# MCU.net
KiCad netlist of a schematic drawn in Altium Designer
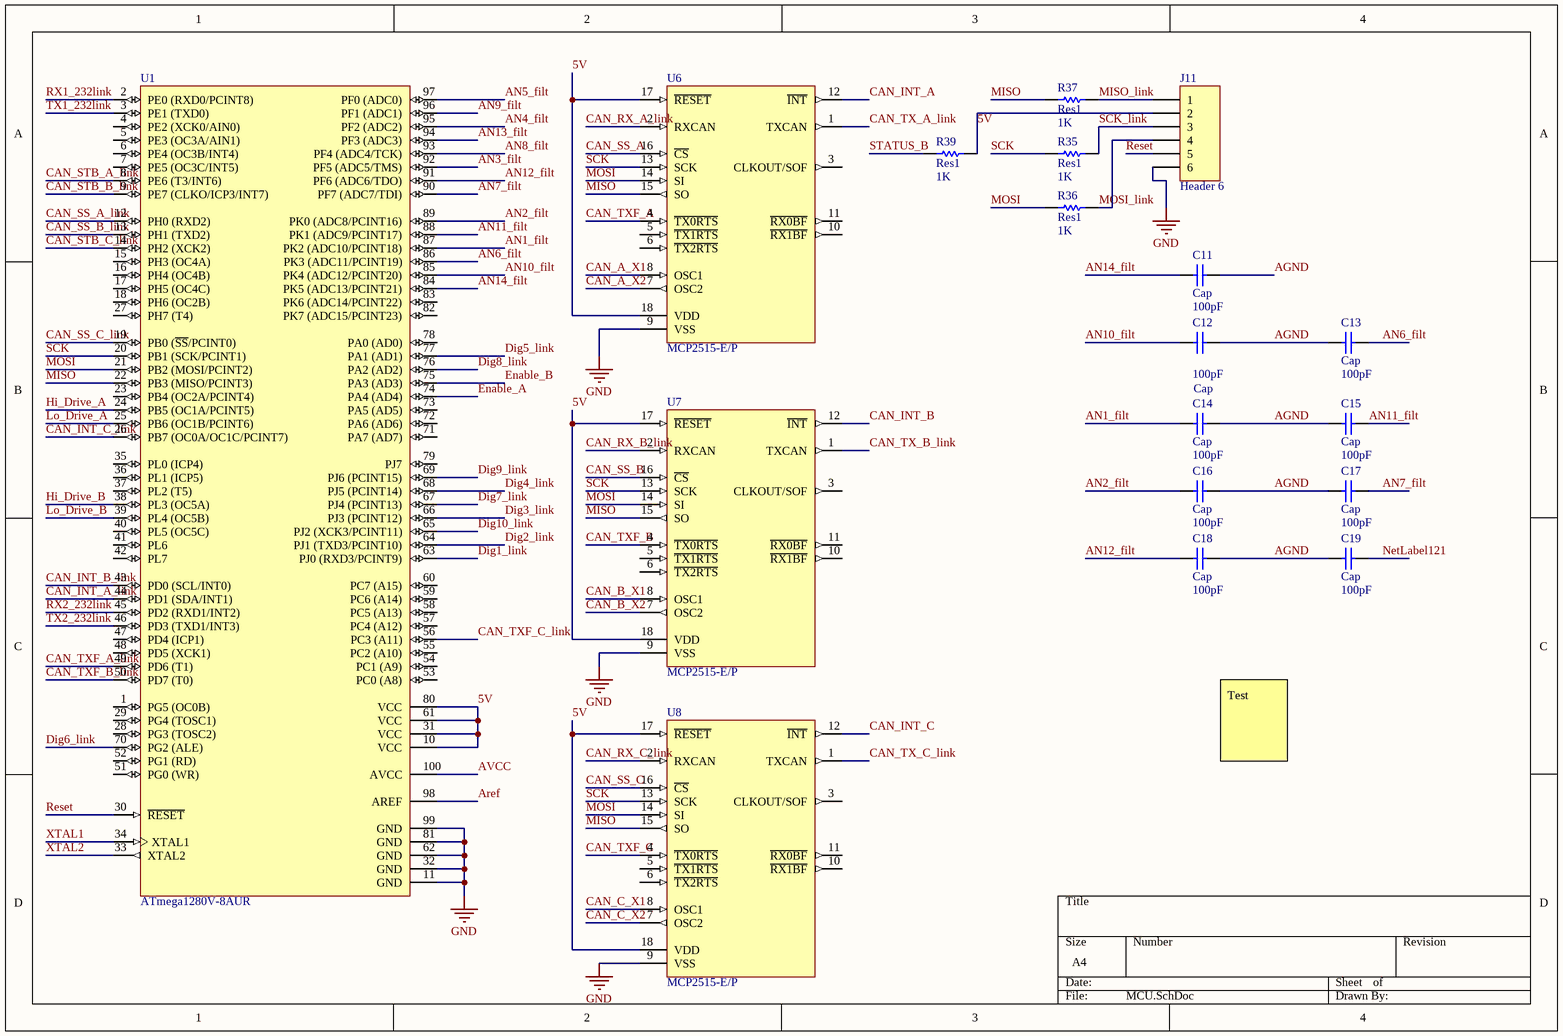
[diagram p0: MCU.SchDoc]

(export (version "E")
  (design (tool "Eeschema 10.0.6"))
  (components
    (comp (ref "C11")
      (value "Cap")
      (footprint "RAD-0.3")
      (description "Capacitor")
      (fields (field (name "ALTIUM_VALUE") "100pF") (field (name "PUBLISHER") "Altium Limited"))
      (libsource (lib "Miscellaneous Devices") (part "Cap"))
    )
    (comp (ref "C12")
      (value "Cap")
      (footprint "RAD-0.3")
      (description "Capacitor")
      (fields (field (name "ALTIUM_VALUE") "100pF") (field (name "PUBLISHER") "Altium Limited"))
      (libsource (lib "Miscellaneous Devices") (part "Cap"))
    )
    (comp (ref "C13")
      (value "Cap")
      (footprint "RAD-0.3")
      (description "Capacitor")
      (fields (field (name "ALTIUM_VALUE") "100pF") (field (name "PUBLISHER") "Altium Limited"))
      (libsource (lib "Miscellaneous Devices") (part "Cap"))
    )
    (comp (ref "C14")
      (value "Cap")
      (footprint "RAD-0.3")
      (description "Capacitor")
      (fields (field (name "ALTIUM_VALUE") "100pF") (field (name "PUBLISHER") "Altium Limited"))
      (libsource (lib "Miscellaneous Devices") (part "Cap"))
    )
    (comp (ref "C15")
      (value "Cap")
      (footprint "RAD-0.3")
      (description "Capacitor")
      (fields (field (name "ALTIUM_VALUE") "100pF") (field (name "PUBLISHER") "Altium Limited"))
      (libsource (lib "Miscellaneous Devices") (part "Cap"))
    )
    (comp (ref "C16")
      (value "Cap")
      (footprint "RAD-0.3")
      (description "Capacitor")
      (fields (field (name "ALTIUM_VALUE") "100pF") (field (name "PUBLISHER") "Altium Limited"))
      (libsource (lib "Miscellaneous Devices") (part "Cap"))
    )
    (comp (ref "C17")
      (value "Cap")
      (footprint "RAD-0.3")
      (description "Capacitor")
      (fields (field (name "ALTIUM_VALUE") "100pF") (field (name "PUBLISHER") "Altium Limited"))
      (libsource (lib "Miscellaneous Devices") (part "Cap"))
    )
    (comp (ref "C18")
      (value "Cap")
      (footprint "RAD-0.3")
      (description "Capacitor")
      (fields (field (name "ALTIUM_VALUE") "100pF") (field (name "PUBLISHER") "Altium Limited"))
      (libsource (lib "Miscellaneous Devices") (part "Cap"))
    )
    (comp (ref "C19")
      (value "Cap")
      (footprint "RAD-0.3")
      (description "Capacitor")
      (fields (field (name "ALTIUM_VALUE") "100pF") (field (name "PUBLISHER") "Altium Limited"))
      (libsource (lib "Miscellaneous Devices") (part "Cap"))
    )
    (comp (ref "J11")
      (value "Header 6")
      (footprint "HDR1X6")
      (description "Header, 6-Pin")
      (fields (field (name "PUBLISHER") "Altium Limited"))
      (libsource (lib "Miscellaneous Connectors") (part "Header 6"))
    )
    (comp (ref "R35")
      (value "Res1")
      (footprint "AXIAL-0.3")
      (description "Resistor")
      (fields (field (name "ALTIUM_VALUE") "1K") (field (name "PUBLISHER") "Altium Limited"))
      (libsource (lib "Miscellaneous Devices") (part "Res1"))
    )
    (comp (ref "R36")
      (value "Res1")
      (footprint "AXIAL-0.3")
      (description "Resistor")
      (fields (field (name "ALTIUM_VALUE") "1K") (field (name "PUBLISHER") "Altium Limited"))
      (libsource (lib "Miscellaneous Devices") (part "Res1"))
    )
    (comp (ref "R37")
      (value "Res1")
      (footprint "AXIAL-0.3")
      (description "Resistor")
      (fields (field (name "ALTIUM_VALUE") "1K") (field (name "PUBLISHER") "Altium Limited"))
      (libsource (lib "Miscellaneous Devices") (part "Res1"))
    )
    (comp (ref "R39")
      (value "Res1")
      (footprint "AXIAL-0.3")
      (description "Resistor")
      (fields (field (name "ALTIUM_VALUE") "1K") (field (name "PUBLISHER") "Altium Limited"))
      (libsource (lib "Miscellaneous Devices") (part "Res1"))
    )
    (comp (ref "U1")
      (value "ATmega1280V-8AUR")
      (footprint "100A_M")
      (libsource (lib "Altium Content Vault") (part "MC-8B-ATM640-SQ100"))
    )
    (comp (ref "U6")
      (value "MCP2515-E/P")
      (footprint "PDIP300-P18")
      (description "Stand-Alone CAN Controller With SPI Interface, 18-Pin PDIP, Extended Temperature")
      (libsource (lib "Altium Content Vault") (part "COM-CAN-MCP2515-18"))
    )
    (comp (ref "U7")
      (value "MCP2515-E/P")
      (footprint "PDIP300-P18")
      (description "Stand-Alone CAN Controller With SPI Interface, 18-Pin PDIP, Extended Temperature")
      (libsource (lib "Altium Content Vault") (part "COM-CAN-MCP2515-18"))
    )
    (comp (ref "U8")
      (value "MCP2515-E/P")
      (footprint "PDIP300-P18")
      (description "Stand-Alone CAN Controller With SPI Interface, 18-Pin PDIP, Extended Temperature")
      (libsource (lib "Altium Content Vault") (part "COM-CAN-MCP2515-18"))
    )
  )
  (nets
    (net (code "1") (name "/5V") (class "Default")
      (node (ref "J11") (pin "2") (pinfunction "2_2") (pintype "passive"))
      (node (ref "R39") (pin "2") (pinfunction "2_2") (pintype "passive"))
      (node (ref "U1") (pin "10") (pinfunction "VCC_10") (pintype "power_in"))
      (node (ref "U1") (pin "31") (pinfunction "VCC_31") (pintype "power_in"))
      (node (ref "U1") (pin "61") (pinfunction "VCC_61") (pintype "power_in"))
      (node (ref "U1") (pin "80") (pinfunction "VCC_80") (pintype "power_in"))
      (node (ref "U6") (pin "17") (pinfunction "~{RESET}_17") (pintype "input"))
      (node (ref "U6") (pin "18") (pinfunction "VDD_18") (pintype "power_in"))
      (node (ref "U7") (pin "17") (pinfunction "~{RESET}_17") (pintype "input"))
      (node (ref "U7") (pin "18") (pinfunction "VDD_18") (pintype "power_in"))
      (node (ref "U8") (pin "17") (pinfunction "~{RESET}_17") (pintype "input"))
      (node (ref "U8") (pin "18") (pinfunction "VDD_18") (pintype "power_in"))
    )
    (net (code "2") (name "/AGND") (class "Default")
      (node (ref "C11") (pin "2") (pinfunction "2_2") (pintype "passive"))
      (node (ref "C12") (pin "2") (pinfunction "2_2") (pintype "passive"))
      (node (ref "C13") (pin "1") (pinfunction "1_1") (pintype "passive"))
      (node (ref "C14") (pin "2") (pinfunction "2_2") (pintype "passive"))
      (node (ref "C15") (pin "1") (pinfunction "1_1") (pintype "passive"))
      (node (ref "C16") (pin "2") (pinfunction "2_2") (pintype "passive"))
      (node (ref "C17") (pin "1") (pinfunction "1_1") (pintype "passive"))
      (node (ref "C18") (pin "2") (pinfunction "2_2") (pintype "passive"))
      (node (ref "C19") (pin "1") (pinfunction "1_1") (pintype "passive"))
    )
    (net (code "3") (name "/AN1_filt") (class "Default")
      (node (ref "C14") (pin "1") (pinfunction "1_1") (pintype "passive"))
      (node (ref "U1") (pin "87") (pinfunction "PK2_(ADC10/PCINT18)_87") (pintype "bidirectional"))
    )
    (net (code "4") (name "/AN2_filt") (class "Default")
      (node (ref "C16") (pin "1") (pinfunction "1_1") (pintype "passive"))
      (node (ref "U1") (pin "89") (pinfunction "PK0_(ADC8/PCINT16)_89") (pintype "bidirectional"))
    )
    (net (code "5") (name "/AN3_filt") (class "Default")
      (node (ref "U1") (pin "92") (pinfunction "PF5_(ADC5/TMS)_92") (pintype "bidirectional"))
    )
    (net (code "6") (name "/AN4_filt") (class "Default")
      (node (ref "U1") (pin "95") (pinfunction "PF2_(ADC2)_95") (pintype "bidirectional"))
    )
    (net (code "7") (name "/AN5_filt") (class "Default")
      (node (ref "U1") (pin "97") (pinfunction "PF0_(ADC0)_97") (pintype "bidirectional"))
    )
    (net (code "8") (name "/AN6_filt") (class "Default")
      (node (ref "C13") (pin "2") (pinfunction "2_2") (pintype "passive"))
      (node (ref "U1") (pin "86") (pinfunction "PK3_(ADC11/PCINT19)_86") (pintype "bidirectional"))
    )
    (net (code "9") (name "/AN7_filt") (class "Default")
      (node (ref "C17") (pin "2") (pinfunction "2_2") (pintype "passive"))
      (node (ref "U1") (pin "90") (pinfunction "PF7_(ADC7/TDI)_90") (pintype "bidirectional"))
    )
    (net (code "10") (name "/AN8_filt") (class "Default")
      (node (ref "U1") (pin "93") (pinfunction "PF4_(ADC4/TCK)_93") (pintype "bidirectional"))
    )
    (net (code "11") (name "/AN9_filt") (class "Default")
      (node (ref "U1") (pin "96") (pinfunction "PF1_(ADC1)_96") (pintype "bidirectional"))
    )
    (net (code "12") (name "/AN10_filt") (class "Default")
      (node (ref "C12") (pin "1") (pinfunction "1_1") (pintype "passive"))
      (node (ref "U1") (pin "85") (pinfunction "PK4_(ADC12/PCINT20)_85") (pintype "bidirectional"))
    )
    (net (code "13") (name "/AN11_filt") (class "Default")
      (node (ref "C15") (pin "2") (pinfunction "2_2") (pintype "passive"))
      (node (ref "U1") (pin "88") (pinfunction "PK1_(ADC9/PCINT17)_88") (pintype "bidirectional"))
    )
    (net (code "14") (name "/AN12_filt") (class "Default")
      (node (ref "C18") (pin "1") (pinfunction "1_1") (pintype "passive"))
      (node (ref "U1") (pin "91") (pinfunction "PF6_(ADC6/TDO)_91") (pintype "bidirectional"))
    )
    (net (code "15") (name "/AN13_filt") (class "Default")
      (node (ref "U1") (pin "94") (pinfunction "PF3_(ADC3)_94") (pintype "bidirectional"))
    )
    (net (code "16") (name "/AN14_filt") (class "Default")
      (node (ref "C11") (pin "1") (pinfunction "1_1") (pintype "passive"))
      (node (ref "U1") (pin "84") (pinfunction "PK5_(ADC13/PCINT21)_84") (pintype "bidirectional"))
    )
    (net (code "17") (name "/AVCC") (class "Default")
      (node (ref "U1") (pin "100") (pinfunction "AVCC_100") (pintype "power_in"))
    )
    (net (code "18") (name "/Aref") (class "Default")
      (node (ref "U1") (pin "98") (pinfunction "AREF_98") (pintype "power_in"))
    )
    (net (code "19") (name "/CAN_A_X1") (class "Default")
      (node (ref "U6") (pin "8") (pinfunction "OSC1_8") (pintype "input"))
    )
    (net (code "20") (name "/CAN_A_X2") (class "Default")
      (node (ref "U6") (pin "7") (pinfunction "OSC2_7") (pintype "output"))
    )
    (net (code "21") (name "/CAN_B_X1") (class "Default")
      (node (ref "U7") (pin "8") (pinfunction "OSC1_8") (pintype "input"))
    )
    (net (code "22") (name "/CAN_B_X2") (class "Default")
      (node (ref "U7") (pin "7") (pinfunction "OSC2_7") (pintype "output"))
    )
    (net (code "23") (name "/CAN_C_X1") (class "Default")
      (node (ref "U8") (pin "8") (pinfunction "OSC1_8") (pintype "input"))
    )
    (net (code "24") (name "/CAN_C_X2") (class "Default")
      (node (ref "U8") (pin "7") (pinfunction "OSC2_7") (pintype "output"))
    )
    (net (code "25") (name "/CAN_INT_A") (class "Default")
      (node (ref "U6") (pin "12") (pinfunction "~{INT}_12") (pintype "output"))
    )
    (net (code "26") (name "/CAN_INT_A_link") (class "Default")
      (node (ref "U1") (pin "44") (pinfunction "PD1_(SDA/INT1)_44") (pintype "bidirectional"))
    )
    (net (code "27") (name "/CAN_INT_B") (class "Default")
      (node (ref "U7") (pin "12") (pinfunction "~{INT}_12") (pintype "output"))
    )
    (net (code "28") (name "/CAN_INT_B_link") (class "Default")
      (node (ref "U1") (pin "43") (pinfunction "PD0_(SCL/INT0)_43") (pintype "bidirectional"))
    )
    (net (code "29") (name "/CAN_INT_C") (class "Default")
      (node (ref "U8") (pin "12") (pinfunction "~{INT}_12") (pintype "output"))
    )
    (net (code "30") (name "/CAN_INT_C_link") (class "Default")
      (node (ref "U1") (pin "26") (pinfunction "PB7_(OC0A/OC1C/PCINT7)_26") (pintype "bidirectional"))
    )
    (net (code "31") (name "/CAN_RX_A_link") (class "Default")
      (node (ref "U6") (pin "2") (pinfunction "RXCAN_2") (pintype "input"))
    )
    (net (code "32") (name "/CAN_RX_B_link") (class "Default")
      (node (ref "U7") (pin "2") (pinfunction "RXCAN_2") (pintype "input"))
    )
    (net (code "33") (name "/CAN_RX_C_link") (class "Default")
      (node (ref "U8") (pin "2") (pinfunction "RXCAN_2") (pintype "input"))
    )
    (net (code "34") (name "/CAN_SS_A") (class "Default")
      (node (ref "U6") (pin "16") (pinfunction "~{CS}_16") (pintype "input"))
    )
    (net (code "35") (name "/CAN_SS_A_link") (class "Default")
      (node (ref "U1") (pin "12") (pinfunction "PH0_(RXD2)_12") (pintype "bidirectional"))
    )
    (net (code "36") (name "/CAN_SS_B") (class "Default")
      (node (ref "U7") (pin "16") (pinfunction "~{CS}_16") (pintype "input"))
    )
    (net (code "37") (name "/CAN_SS_B_link") (class "Default")
      (node (ref "U1") (pin "13") (pinfunction "PH1_(TXD2)_13") (pintype "bidirectional"))
    )
    (net (code "38") (name "/CAN_SS_C") (class "Default")
      (node (ref "U8") (pin "16") (pinfunction "~{CS}_16") (pintype "input"))
    )
    (net (code "39") (name "/CAN_SS_C_link") (class "Default")
      (node (ref "U1") (pin "19") (pinfunction "PB0_(~{SS}/PCINT0)_19") (pintype "bidirectional"))
    )
    (net (code "40") (name "/CAN_STB_A_link") (class "Default")
      (node (ref "U1") (pin "8") (pinfunction "PE6_(T3/INT6)_8") (pintype "bidirectional"))
    )
    (net (code "41") (name "/CAN_STB_B_link") (class "Default")
      (node (ref "U1") (pin "9") (pinfunction "PE7_(CLKO/ICP3/INT7)_9") (pintype "bidirectional"))
    )
    (net (code "42") (name "/CAN_STB_C_link") (class "Default")
      (node (ref "U1") (pin "14") (pinfunction "PH2_(XCK2)_14") (pintype "bidirectional"))
    )
    (net (code "43") (name "/CAN_TXF_A") (class "Default")
      (node (ref "U6") (pin "4") (pinfunction "~{TX0RTS}_4") (pintype "input"))
    )
    (net (code "44") (name "/CAN_TXF_A_link") (class "Default")
      (node (ref "U1") (pin "49") (pinfunction "PD6_(T1)_49") (pintype "bidirectional"))
    )
    (net (code "45") (name "/CAN_TXF_B") (class "Default")
      (node (ref "U7") (pin "4") (pinfunction "~{TX0RTS}_4") (pintype "input"))
    )
    (net (code "46") (name "/CAN_TXF_B_link") (class "Default")
      (node (ref "U1") (pin "50") (pinfunction "PD7_(T0)_50") (pintype "bidirectional"))
    )
    (net (code "47") (name "/CAN_TXF_C") (class "Default")
      (node (ref "U8") (pin "4") (pinfunction "~{TX0RTS}_4") (pintype "input"))
    )
    (net (code "48") (name "/CAN_TXF_C_link") (class "Default")
      (node (ref "U1") (pin "56") (pinfunction "PC3_(A11)_56") (pintype "bidirectional"))
    )
    (net (code "49") (name "/CAN_TX_A_link") (class "Default")
      (node (ref "U6") (pin "1") (pinfunction "TXCAN_1") (pintype "output"))
    )
    (net (code "50") (name "/CAN_TX_B_link") (class "Default")
      (node (ref "U7") (pin "1") (pinfunction "TXCAN_1") (pintype "output"))
    )
    (net (code "51") (name "/CAN_TX_C_link") (class "Default")
      (node (ref "U8") (pin "1") (pinfunction "TXCAN_1") (pintype "output"))
    )
    (net (code "52") (name "/Dig1_link") (class "Default")
      (node (ref "U1") (pin "63") (pinfunction "PJ0_(RXD3/PCINT9)_63") (pintype "bidirectional"))
    )
    (net (code "53") (name "/Dig2_link") (class "Default")
      (node (ref "U1") (pin "64") (pinfunction "PJ1_(TXD3/PCINT10)_64") (pintype "bidirectional"))
    )
    (net (code "54") (name "/Dig3_link") (class "Default")
      (node (ref "U1") (pin "66") (pinfunction "PJ3_(PCINT12)_66") (pintype "bidirectional"))
    )
    (net (code "55") (name "/Dig4_link") (class "Default")
      (node (ref "U1") (pin "68") (pinfunction "PJ5_(PCINT14)_68") (pintype "bidirectional"))
    )
    (net (code "56") (name "/Dig5_link") (class "Default")
      (node (ref "U1") (pin "77") (pinfunction "PA1_(AD1)_77") (pintype "bidirectional"))
    )
    (net (code "57") (name "/Dig6_link") (class "Default")
      (node (ref "U1") (pin "70") (pinfunction "PG2_(ALE)_70") (pintype "bidirectional"))
    )
    (net (code "58") (name "/Dig7_link") (class "Default")
      (node (ref "U1") (pin "67") (pinfunction "PJ4_(PCINT13)_67") (pintype "bidirectional"))
    )
    (net (code "59") (name "/Dig8_link") (class "Default")
      (node (ref "U1") (pin "76") (pinfunction "PA2_(AD2)_76") (pintype "bidirectional"))
    )
    (net (code "60") (name "/Dig9_link") (class "Default")
      (node (ref "U1") (pin "69") (pinfunction "PJ6_(PCINT15)_69") (pintype "bidirectional"))
    )
    (net (code "61") (name "/Dig10_link") (class "Default")
      (node (ref "U1") (pin "65") (pinfunction "PJ2_(XCK3/PCINT11)_65") (pintype "bidirectional"))
    )
    (net (code "62") (name "/Enable_A") (class "Default")
      (node (ref "U1") (pin "74") (pinfunction "PA4_(AD4)_74") (pintype "bidirectional"))
    )
    (net (code "63") (name "/Enable_B") (class "Default")
      (node (ref "U1") (pin "75") (pinfunction "PA3_(AD3)_75") (pintype "bidirectional"))
    )
    (net (code "64") (name "/Hi_Drive_A") (class "Default")
      (node (ref "U1") (pin "24") (pinfunction "PB5_(OC1A/PCINT5)_24") (pintype "bidirectional"))
    )
    (net (code "65") (name "/Hi_Drive_B") (class "Default")
      (node (ref "U1") (pin "38") (pinfunction "PL3_(OC5A)_38") (pintype "bidirectional"))
    )
    (net (code "66") (name "/Lo_Drive_A") (class "Default")
      (node (ref "U1") (pin "25") (pinfunction "PB6_(OC1B/PCINT6)_25") (pintype "bidirectional"))
    )
    (net (code "67") (name "/Lo_Drive_B") (class "Default")
      (node (ref "U1") (pin "39") (pinfunction "PL4_(OC5B)_39") (pintype "bidirectional"))
    )
    (net (code "68") (name "/MISO") (class "Default")
      (node (ref "R37") (pin "1") (pinfunction "1_1") (pintype "passive"))
      (node (ref "U1") (pin "22") (pinfunction "PB3_(MISO/PCINT3)_22") (pintype "bidirectional"))
      (node (ref "U6") (pin "15") (pinfunction "SO_15") (pintype "output"))
      (node (ref "U7") (pin "15") (pinfunction "SO_15") (pintype "output"))
      (node (ref "U8") (pin "15") (pinfunction "SO_15") (pintype "output"))
    )
    (net (code "69") (name "/MISO_link") (class "Default")
      (node (ref "J11") (pin "1") (pinfunction "1_1") (pintype "passive"))
      (node (ref "R37") (pin "2") (pinfunction "2_2") (pintype "passive"))
    )
    (net (code "70") (name "/MOSI") (class "Default")
      (node (ref "R36") (pin "1") (pinfunction "1_1") (pintype "passive"))
      (node (ref "U1") (pin "21") (pinfunction "PB2_(MOSI/PCINT2)_21") (pintype "bidirectional"))
      (node (ref "U6") (pin "14") (pinfunction "SI_14") (pintype "input"))
      (node (ref "U7") (pin "14") (pinfunction "SI_14") (pintype "input"))
      (node (ref "U8") (pin "14") (pinfunction "SI_14") (pintype "input"))
    )
    (net (code "71") (name "/MOSI_link") (class "Default")
      (node (ref "J11") (pin "4") (pinfunction "4_4") (pintype "passive"))
      (node (ref "R36") (pin "2") (pinfunction "2_2") (pintype "passive"))
    )
    (net (code "72") (name "/NetLabel121") (class "Default")
      (node (ref "C19") (pin "2") (pinfunction "2_2") (pintype "passive"))
    )
    (net (code "73") (name "/RX1_232link") (class "Default")
      (node (ref "U1") (pin "2") (pinfunction "PE0_(RXD0/PCINT8)_2") (pintype "bidirectional"))
    )
    (net (code "74") (name "/RX2_232link") (class "Default")
      (node (ref "U1") (pin "45") (pinfunction "PD2_(RXD1/INT2)_45") (pintype "bidirectional"))
    )
    (net (code "75") (name "/Reset") (class "Default")
      (node (ref "J11") (pin "5") (pinfunction "5_5") (pintype "passive"))
      (node (ref "U1") (pin "30") (pinfunction "~{RESET}_30") (pintype "input"))
    )
    (net (code "76") (name "/SCK") (class "Default")
      (node (ref "R35") (pin "1") (pinfunction "1_1") (pintype "passive"))
      (node (ref "U1") (pin "20") (pinfunction "PB1_(SCK/PCINT1)_20") (pintype "bidirectional"))
      (node (ref "U6") (pin "13") (pinfunction "SCK_13") (pintype "input"))
      (node (ref "U7") (pin "13") (pinfunction "SCK_13") (pintype "input"))
      (node (ref "U8") (pin "13") (pinfunction "SCK_13") (pintype "input"))
    )
    (net (code "77") (name "/SCK_link") (class "Default")
      (node (ref "J11") (pin "3") (pinfunction "3_3") (pintype "passive"))
      (node (ref "R35") (pin "2") (pinfunction "2_2") (pintype "passive"))
    )
    (net (code "78") (name "/STATUS_B") (class "Default")
      (node (ref "R39") (pin "1") (pinfunction "1_1") (pintype "passive"))
    )
    (net (code "79") (name "/TX1_232link") (class "Default")
      (node (ref "U1") (pin "3") (pinfunction "PE1_(TXD0)_3") (pintype "bidirectional"))
    )
    (net (code "80") (name "/TX2_232link") (class "Default")
      (node (ref "U1") (pin "46") (pinfunction "PD3_(TXD1/INT3)_46") (pintype "bidirectional"))
    )
    (net (code "81") (name "/XTAL1") (class "Default")
      (node (ref "U1") (pin "34") (pinfunction "XTAL1_34") (pintype "input"))
    )
    (net (code "82") (name "/XTAL2") (class "Default")
      (node (ref "U1") (pin "33") (pinfunction "XTAL2_33") (pintype "output"))
    )
    (net (code "83") (name "GND") (class "Default")
      (node (ref "J11") (pin "6") (pinfunction "6_6") (pintype "passive"))
      (node (ref "U1") (pin "11") (pinfunction "GND_11") (pintype "power_in"))
      (node (ref "U1") (pin "32") (pinfunction "GND_32") (pintype "power_in"))
      (node (ref "U1") (pin "62") (pinfunction "GND_62") (pintype "power_in"))
      (node (ref "U1") (pin "81") (pinfunction "GND_81") (pintype "power_in"))
      (node (ref "U1") (pin "99") (pinfunction "GND_99") (pintype "power_in"))
      (node (ref "U6") (pin "9") (pinfunction "VSS_9") (pintype "power_in"))
      (node (ref "U7") (pin "9") (pinfunction "VSS_9") (pintype "power_in"))
      (node (ref "U8") (pin "9") (pinfunction "VSS_9") (pintype "power_in"))
    )
    (net (code "84") (name "unconnected-(U1-PA0_(AD0)-Pad78)") (class "Default")
      (node (ref "U1") (pin "78") (pinfunction "PA0_(AD0)_78") (pintype "bidirectional"))
    )
    (net (code "85") (name "unconnected-(U1-PA5_(AD5)-Pad73)") (class "Default")
      (node (ref "U1") (pin "73") (pinfunction "PA5_(AD5)_73") (pintype "bidirectional"))
    )
    (net (code "86") (name "unconnected-(U1-PA6_(AD6)-Pad72)") (class "Default")
      (node (ref "U1") (pin "72") (pinfunction "PA6_(AD6)_72") (pintype "bidirectional"))
    )
    (net (code "87") (name "unconnected-(U1-PA7_(AD7)-Pad71)") (class "Default")
      (node (ref "U1") (pin "71") (pinfunction "PA7_(AD7)_71") (pintype "bidirectional"))
    )
    (net (code "88") (name "unconnected-(U1-PB4_(OC2A{slash}PCINT4)-Pad23)") (class "Default")
      (node (ref "U1") (pin "23") (pinfunction "PB4_(OC2A/PCINT4)_23") (pintype "bidirectional"))
    )
    (net (code "89") (name "unconnected-(U1-PC0_(A8)-Pad53)") (class "Default")
      (node (ref "U1") (pin "53") (pinfunction "PC0_(A8)_53") (pintype "bidirectional"))
    )
    (net (code "90") (name "unconnected-(U1-PC1_(A9)-Pad54)") (class "Default")
      (node (ref "U1") (pin "54") (pinfunction "PC1_(A9)_54") (pintype "bidirectional"))
    )
    (net (code "91") (name "unconnected-(U1-PC2_(A10)-Pad55)") (class "Default")
      (node (ref "U1") (pin "55") (pinfunction "PC2_(A10)_55") (pintype "bidirectional"))
    )
    (net (code "92") (name "unconnected-(U1-PC4_(A12)-Pad57)") (class "Default")
      (node (ref "U1") (pin "57") (pinfunction "PC4_(A12)_57") (pintype "bidirectional"))
    )
    (net (code "93") (name "unconnected-(U1-PC5_(A13)-Pad58)") (class "Default")
      (node (ref "U1") (pin "58") (pinfunction "PC5_(A13)_58") (pintype "bidirectional"))
    )
    (net (code "94") (name "unconnected-(U1-PC6_(A14)-Pad59)") (class "Default")
      (node (ref "U1") (pin "59") (pinfunction "PC6_(A14)_59") (pintype "bidirectional"))
    )
    (net (code "95") (name "unconnected-(U1-PC7_(A15)-Pad60)") (class "Default")
      (node (ref "U1") (pin "60") (pinfunction "PC7_(A15)_60") (pintype "bidirectional"))
    )
    (net (code "96") (name "unconnected-(U1-PD4_(ICP1)-Pad47)") (class "Default")
      (node (ref "U1") (pin "47") (pinfunction "PD4_(ICP1)_47") (pintype "bidirectional"))
    )
    (net (code "97") (name "unconnected-(U1-PD5_(XCK1)-Pad48)") (class "Default")
      (node (ref "U1") (pin "48") (pinfunction "PD5_(XCK1)_48") (pintype "bidirectional"))
    )
    (net (code "98") (name "unconnected-(U1-PE2_(XCK0{slash}AIN0)-Pad4)") (class "Default")
      (node (ref "U1") (pin "4") (pinfunction "PE2_(XCK0/AIN0)_4") (pintype "bidirectional"))
    )
    (net (code "99") (name "unconnected-(U1-PE3_(OC3A{slash}AIN1)-Pad5)") (class "Default")
      (node (ref "U1") (pin "5") (pinfunction "PE3_(OC3A/AIN1)_5") (pintype "bidirectional"))
    )
    (net (code "100") (name "unconnected-(U1-PE4_(OC3B{slash}INT4)-Pad6)") (class "Default")
      (node (ref "U1") (pin "6") (pinfunction "PE4_(OC3B/INT4)_6") (pintype "bidirectional"))
    )
    (net (code "101") (name "unconnected-(U1-PE5_(OC3C{slash}INT5)-Pad7)") (class "Default")
      (node (ref "U1") (pin "7") (pinfunction "PE5_(OC3C/INT5)_7") (pintype "bidirectional"))
    )
    (net (code "102") (name "unconnected-(U1-PG0_(WR)-Pad51)") (class "Default")
      (node (ref "U1") (pin "51") (pinfunction "PG0_(WR)_51") (pintype "bidirectional"))
    )
    (net (code "103") (name "unconnected-(U1-PG1_(RD)-Pad52)") (class "Default")
      (node (ref "U1") (pin "52") (pinfunction "PG1_(RD)_52") (pintype "bidirectional"))
    )
    (net (code "104") (name "unconnected-(U1-PG3_(TOSC2)-Pad28)") (class "Default")
      (node (ref "U1") (pin "28") (pinfunction "PG3_(TOSC2)_28") (pintype "bidirectional"))
    )
    (net (code "105") (name "unconnected-(U1-PG4_(TOSC1)-Pad29)") (class "Default")
      (node (ref "U1") (pin "29") (pinfunction "PG4_(TOSC1)_29") (pintype "bidirectional"))
    )
    (net (code "106") (name "unconnected-(U1-PG5_(OC0B)-Pad1)") (class "Default")
      (node (ref "U1") (pin "1") (pinfunction "PG5_(OC0B)_1") (pintype "bidirectional"))
    )
    (net (code "107") (name "unconnected-(U1-PH3_(OC4A)-Pad15)") (class "Default")
      (node (ref "U1") (pin "15") (pinfunction "PH3_(OC4A)_15") (pintype "bidirectional"))
    )
    (net (code "108") (name "unconnected-(U1-PH4_(OC4B)-Pad16)") (class "Default")
      (node (ref "U1") (pin "16") (pinfunction "PH4_(OC4B)_16") (pintype "bidirectional"))
    )
    (net (code "109") (name "unconnected-(U1-PH5_(OC4C)-Pad17)") (class "Default")
      (node (ref "U1") (pin "17") (pinfunction "PH5_(OC4C)_17") (pintype "bidirectional"))
    )
    (net (code "110") (name "unconnected-(U1-PH6_(OC2B)-Pad18)") (class "Default")
      (node (ref "U1") (pin "18") (pinfunction "PH6_(OC2B)_18") (pintype "bidirectional"))
    )
    (net (code "111") (name "unconnected-(U1-PH7_(T4)-Pad27)") (class "Default")
      (node (ref "U1") (pin "27") (pinfunction "PH7_(T4)_27") (pintype "bidirectional"))
    )
    (net (code "112") (name "unconnected-(U1-PJ7-Pad79)") (class "Default")
      (node (ref "U1") (pin "79") (pinfunction "PJ7_79") (pintype "bidirectional"))
    )
    (net (code "113") (name "unconnected-(U1-PK6_(ADC14{slash}PCINT22)-Pad83)") (class "Default")
      (node (ref "U1") (pin "83") (pinfunction "PK6_(ADC14/PCINT22)_83") (pintype "bidirectional"))
    )
    (net (code "114") (name "unconnected-(U1-PK7_(ADC15{slash}PCINT23)-Pad82)") (class "Default")
      (node (ref "U1") (pin "82") (pinfunction "PK7_(ADC15/PCINT23)_82") (pintype "bidirectional"))
    )
    (net (code "115") (name "unconnected-(U1-PL0_(ICP4)-Pad35)") (class "Default")
      (node (ref "U1") (pin "35") (pinfunction "PL0_(ICP4)_35") (pintype "bidirectional"))
    )
    (net (code "116") (name "unconnected-(U1-PL1_(ICP5)-Pad36)") (class "Default")
      (node (ref "U1") (pin "36") (pinfunction "PL1_(ICP5)_36") (pintype "bidirectional"))
    )
    (net (code "117") (name "unconnected-(U1-PL2_(T5)-Pad37)") (class "Default")
      (node (ref "U1") (pin "37") (pinfunction "PL2_(T5)_37") (pintype "bidirectional"))
    )
    (net (code "118") (name "unconnected-(U1-PL5_(OC5C)-Pad40)") (class "Default")
      (node (ref "U1") (pin "40") (pinfunction "PL5_(OC5C)_40") (pintype "bidirectional"))
    )
    (net (code "119") (name "unconnected-(U1-PL6-Pad41)") (class "Default")
      (node (ref "U1") (pin "41") (pinfunction "PL6_41") (pintype "bidirectional"))
    )
    (net (code "120") (name "unconnected-(U1-PL7-Pad42)") (class "Default")
      (node (ref "U1") (pin "42") (pinfunction "PL7_42") (pintype "bidirectional"))
    )
    (net (code "121") (name "unconnected-(U6-CLKOUT{slash}SOF-Pad3)") (class "Default")
      (node (ref "U6") (pin "3") (pinfunction "CLKOUT/SOF_3") (pintype "output"))
    )
    (net (code "122") (name "unconnected-(U6-~{RX0BF}-Pad11)") (class "Default")
      (node (ref "U6") (pin "11") (pinfunction "~{RX0BF}_11") (pintype "output"))
    )
    (net (code "123") (name "unconnected-(U6-~{RX1BF}-Pad10)") (class "Default")
      (node (ref "U6") (pin "10") (pinfunction "~{RX1BF}_10") (pintype "output"))
    )
    (net (code "124") (name "unconnected-(U6-~{TX1RTS}-Pad5)") (class "Default")
      (node (ref "U6") (pin "5") (pinfunction "~{TX1RTS}_5") (pintype "input"))
    )
    (net (code "125") (name "unconnected-(U6-~{TX2RTS}-Pad6)") (class "Default")
      (node (ref "U6") (pin "6") (pinfunction "~{TX2RTS}_6") (pintype "input"))
    )
    (net (code "126") (name "unconnected-(U7-CLKOUT{slash}SOF-Pad3)") (class "Default")
      (node (ref "U7") (pin "3") (pinfunction "CLKOUT/SOF_3") (pintype "output"))
    )
    (net (code "127") (name "unconnected-(U7-~{RX0BF}-Pad11)") (class "Default")
      (node (ref "U7") (pin "11") (pinfunction "~{RX0BF}_11") (pintype "output"))
    )
    (net (code "128") (name "unconnected-(U7-~{RX1BF}-Pad10)") (class "Default")
      (node (ref "U7") (pin "10") (pinfunction "~{RX1BF}_10") (pintype "output"))
    )
    (net (code "129") (name "unconnected-(U7-~{TX1RTS}-Pad5)") (class "Default")
      (node (ref "U7") (pin "5") (pinfunction "~{TX1RTS}_5") (pintype "input"))
    )
    (net (code "130") (name "unconnected-(U7-~{TX2RTS}-Pad6)") (class "Default")
      (node (ref "U7") (pin "6") (pinfunction "~{TX2RTS}_6") (pintype "input"))
    )
    (net (code "131") (name "unconnected-(U8-CLKOUT{slash}SOF-Pad3)") (class "Default")
      (node (ref "U8") (pin "3") (pinfunction "CLKOUT/SOF_3") (pintype "output"))
    )
    (net (code "132") (name "unconnected-(U8-~{RX0BF}-Pad11)") (class "Default")
      (node (ref "U8") (pin "11") (pinfunction "~{RX0BF}_11") (pintype "output"))
    )
    (net (code "133") (name "unconnected-(U8-~{RX1BF}-Pad10)") (class "Default")
      (node (ref "U8") (pin "10") (pinfunction "~{RX1BF}_10") (pintype "output"))
    )
    (net (code "134") (name "unconnected-(U8-~{TX1RTS}-Pad5)") (class "Default")
      (node (ref "U8") (pin "5") (pinfunction "~{TX1RTS}_5") (pintype "input"))
    )
    (net (code "135") (name "unconnected-(U8-~{TX2RTS}-Pad6)") (class "Default")
      (node (ref "U8") (pin "6") (pinfunction "~{TX2RTS}_6") (pintype "input"))
    )
  )
)
